# main.net
KiCad netlist of a schematic drawn in Altium Designer
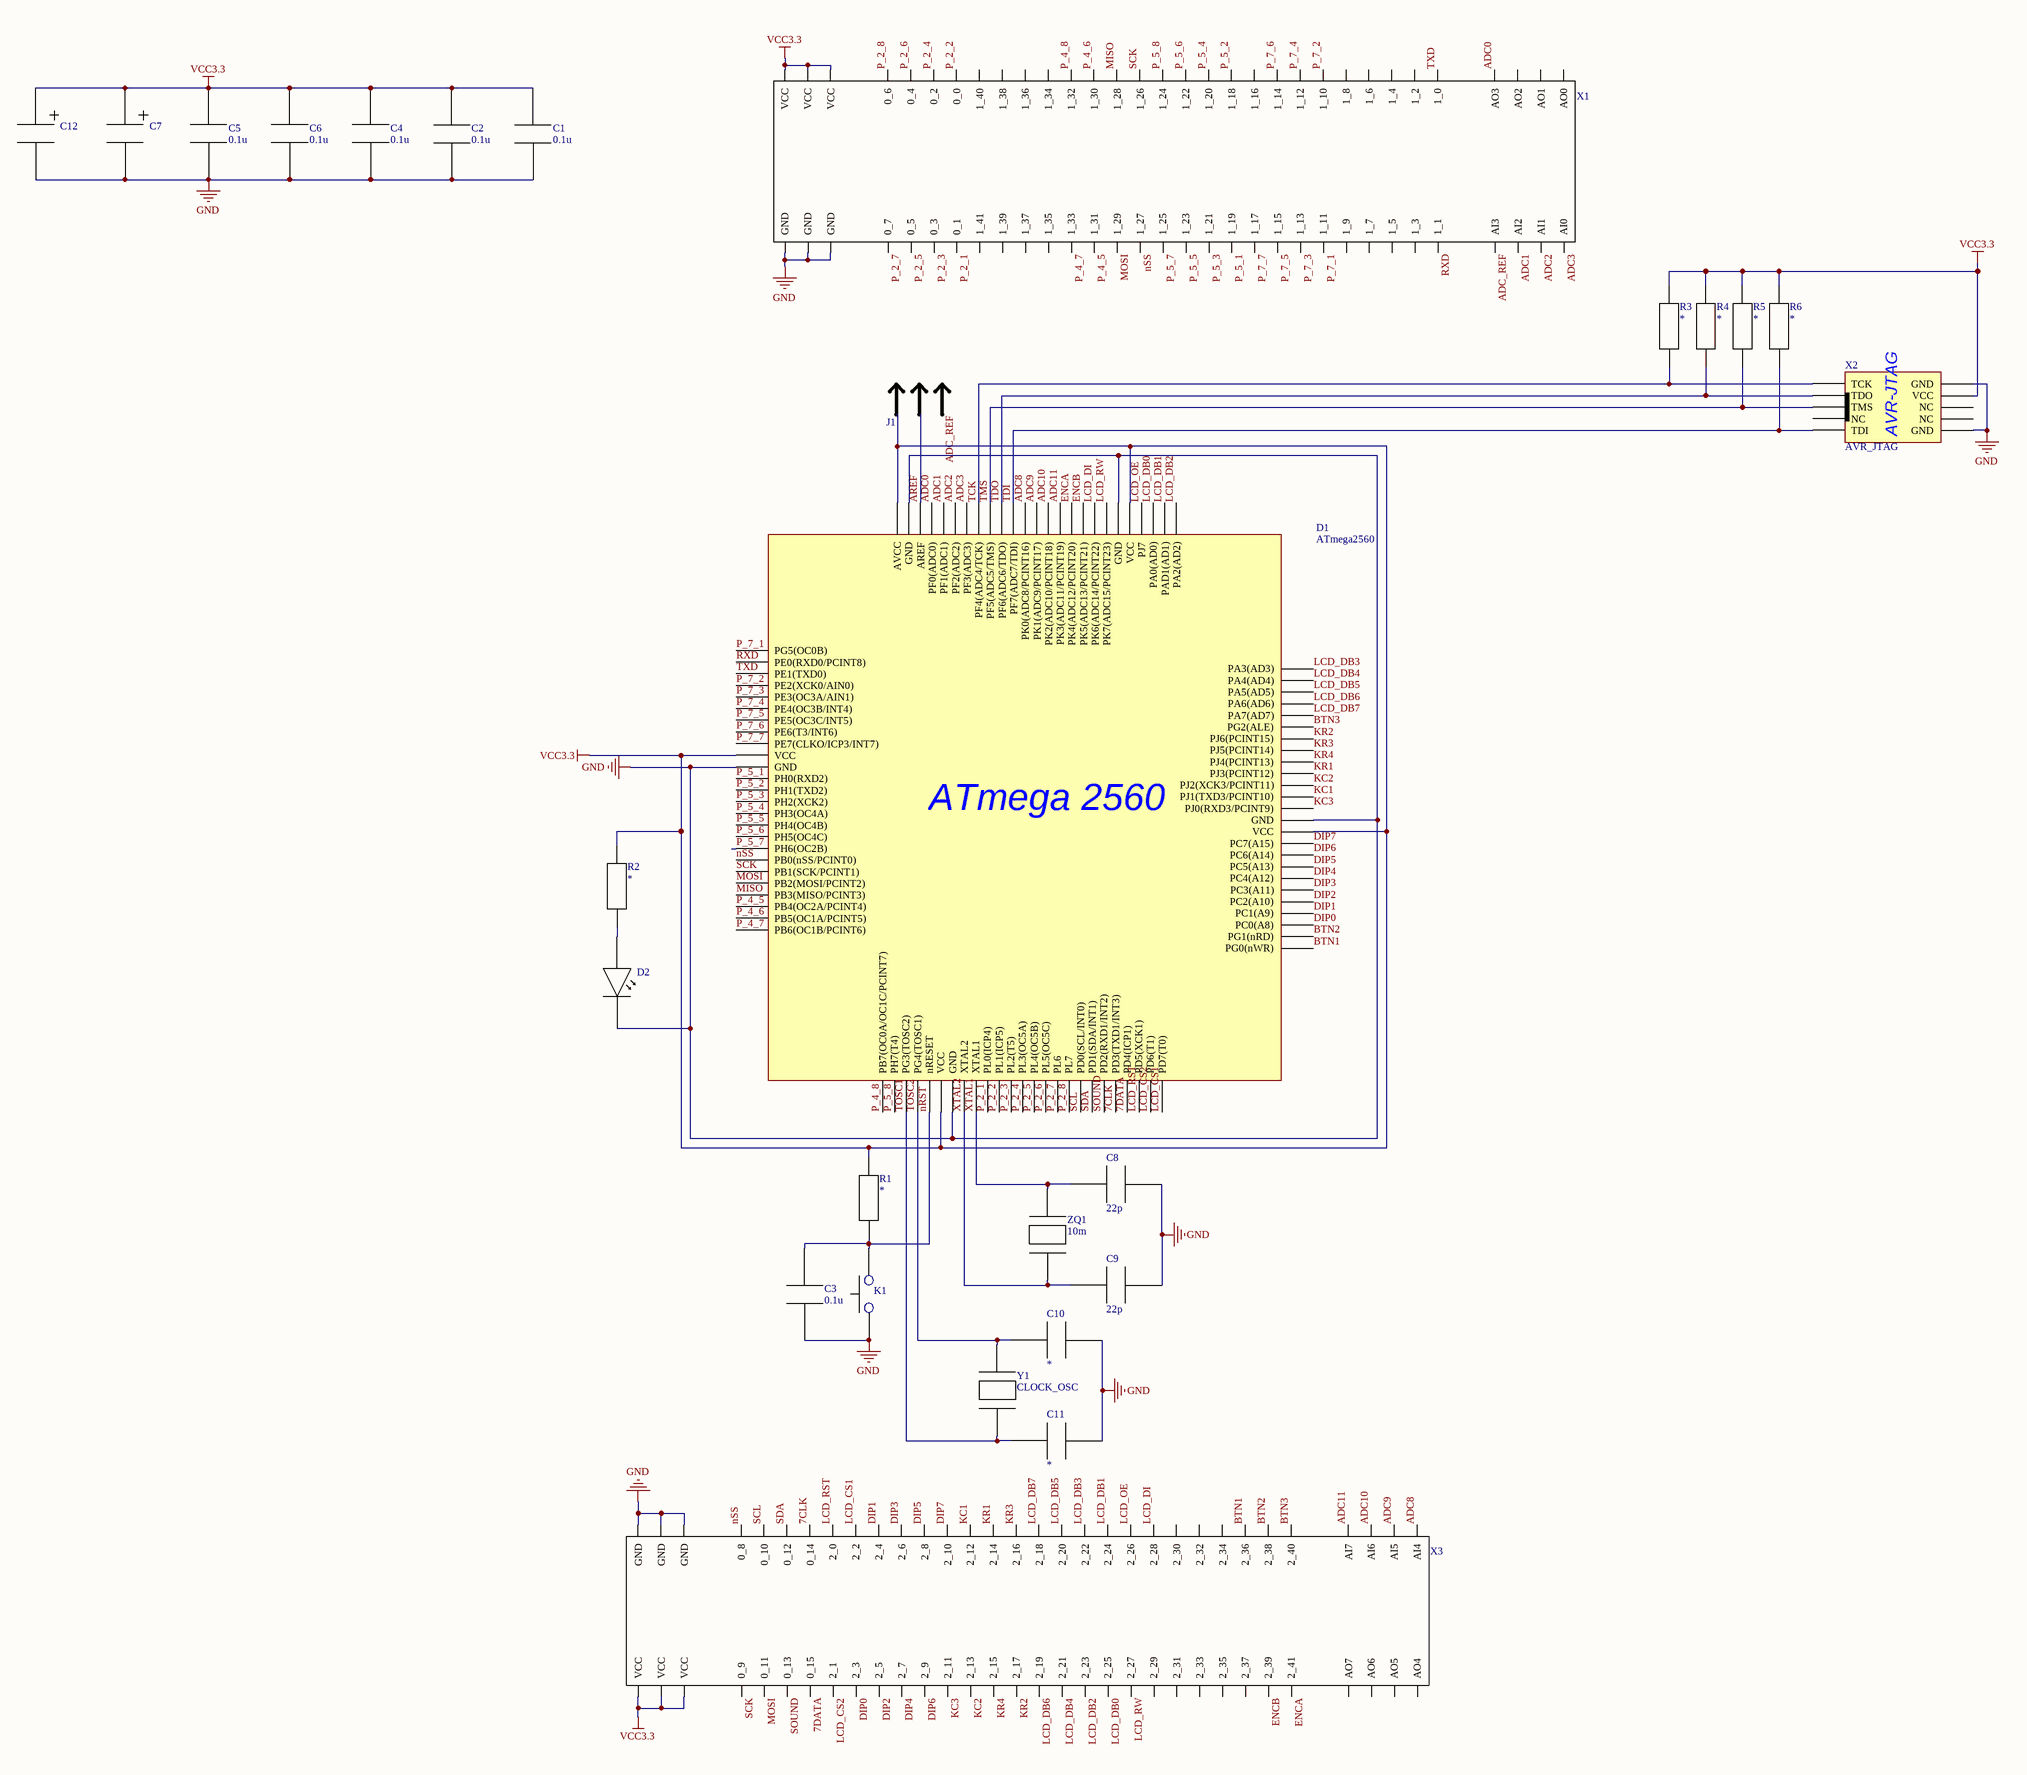
[diagram p0: main.SchDoc]

(export (version "E")
  (design (tool "Eeschema 10.0.6"))
  (components
    (comp (ref "C1")
      (value "0.1u")
      (footprint "0805")
      (description "0805 ceramic capacitor")
      (libsource (lib "ELVmega") (part "C0805"))
    )
    (comp (ref "C2")
      (value "0.1u")
      (footprint "0805")
      (description "0805 ceramic capacitor")
      (libsource (lib "ELVmega") (part "C0805"))
    )
    (comp (ref "C3")
      (value "0.1u")
      (footprint "0805")
      (description "0805 ceramic capacitor")
      (libsource (lib "ELVmega") (part "C0805"))
    )
    (comp (ref "C4")
      (value "0.1u")
      (footprint "0805")
      (description "0805 ceramic capacitor")
      (libsource (lib "ELVmega") (part "C0805"))
    )
    (comp (ref "C5")
      (value "0.1u")
      (footprint "0805")
      (description "0805 ceramic capacitor")
      (libsource (lib "ELVmega") (part "C0805"))
    )
    (comp (ref "C6")
      (value "0.1u")
      (footprint "0805")
      (description "0805 ceramic capacitor")
      (libsource (lib "ELVmega") (part "C0805"))
    )
    (comp (ref "C7")
      (value "C_Ta")
      (footprint "C_Ta")
      (description "tantalum capacitor")
      (libsource (lib "ELVmega") (part "C_Ta"))
    )
    (comp (ref "C8")
      (value "22p")
      (footprint "0805")
      (description "0805 ceramic capacitor")
      (libsource (lib "ELVmega") (part "C0805"))
    )
    (comp (ref "C9")
      (value "22p")
      (footprint "0805")
      (description "0805 ceramic capacitor")
      (libsource (lib "ELVmega") (part "C0805"))
    )
    (comp (ref "C10")
      (value "*")
      (footprint "0805")
      (description "0805 ceramic capacitor")
      (libsource (lib "ELVmega") (part "C0805"))
    )
    (comp (ref "C11")
      (value "*")
      (footprint "0805")
      (description "0805 ceramic capacitor")
      (libsource (lib "ELVmega") (part "C0805"))
    )
    (comp (ref "C12")
      (value "C_Ta")
      (footprint "C_Ta")
      (description "tantalum capacitor")
      (libsource (lib "spels_lib") (part "C_Ta"))
    )
    (comp (ref "D1")
      (value "ATmega2560")
      (footprint "ATmega2560-16AU")
      (libsource (lib "ELVmega") (part "ATmega2560"))
    )
    (comp (ref "D2") (value "LED0805") (footprint "0805") (libsource (lib "ELVmega") (part "LED0805")))
    (comp (ref "J1")
      (value "JUMPER_SWITCH_2S")
      (footprint "JUMPER_SWITCH_2S")
      (description "2 state jumper switch")
      (libsource (lib "ELVmega") (part "JUMPER_SWITCH_2S"))
    )
    (comp (ref "K1")
      (value "SMD_BUTTON")
      (footprint "SMD_BUTTON")
      (description "smd micro button")
      (libsource (lib "ELVmega") (part "SMD_BUTTON"))
    )
    (comp (ref "R1")
      (value "*")
      (footprint "0805")
      (description "0805 resistor")
      (libsource (lib "") (part "R0805_1"))
    )
    (comp (ref "R2")
      (value "*")
      (footprint "0805")
      (description "0805 resistor")
      (libsource (lib "ELVmega") (part "R0805"))
    )
    (comp (ref "R3")
      (value "*")
      (footprint "0805")
      (description "0805 resistor")
      (libsource (lib "") (part "R0805_1"))
    )
    (comp (ref "R4")
      (value "*")
      (footprint "0805")
      (description "0805 resistor")
      (libsource (lib "") (part "R0805_1"))
    )
    (comp (ref "R5")
      (value "*")
      (footprint "0805")
      (description "0805 resistor")
      (libsource (lib "") (part "R0805_1"))
    )
    (comp (ref "R6")
      (value "*")
      (footprint "0805")
      (description "0805 resistor")
      (libsource (lib "") (part "R0805_1"))
    )
    (comp (ref "X1")
      (value "CONNECTOR_TOP")
      (footprint "Connector")
      (description "control board connector")
      (libsource (lib "elvis_lib") (part "CONNECTOR_TOP"))
    )
    (comp (ref "X2") (value "AVR_JTAG") (footprint "JTAG_PLD") (libsource (lib "ELVmega") (part "AVR_JTAG")))
    (comp (ref "X3")
      (value "CONNECTOR_BOTTOM")
      (footprint "Connector")
      (description "control board connector")
      (libsource (lib "elvis_lib") (part "CONNECTOR_BOTTOM"))
    )
    (comp (ref "Y1")
      (value "CLOCK_OSC")
      (footprint "CLOCK_OSC")
      (description "low speed external clock")
      (libsource (lib "ELVmega") (part "CLOCK_OSC"))
    )
    (comp (ref "ZQ1") (value "10m") (footprint "XTAL") (libsource (lib "ELVmega") (part "XTAL")))
  )
  (nets
    (net (code "1") (name "/7CLK") (class "Default")
      (node (ref "D1") (pin "46") (pinfunction "PD3(TXD1/INT3)_46") (pintype "passive"))
      (node (ref "X3") (pin "6") (pinfunction "0_14_6") (pintype "passive"))
    )
    (net (code "2") (name "/7DATA") (class "Default")
      (node (ref "D1") (pin "47") (pinfunction "PD4(ICP1)_47") (pintype "passive"))
      (node (ref "X3") (pin "57") (pinfunction "0_15_57") (pintype "passive"))
    )
    (net (code "3") (name "/ADC0") (class "Default")
      (node (ref "D1") (pin "97") (pinfunction "PF0(ADC0)_97") (pintype "passive"))
      (node (ref "X1") (pin "28") (pinfunction "AO3_28") (pintype "passive"))
    )
    (net (code "4") (name "/ADC1") (class "Default")
      (node (ref "D1") (pin "96") (pinfunction "PF1(ADC1)_96") (pintype "passive"))
      (node (ref "X1") (pin "34") (pinfunction "AI2_34") (pintype "passive"))
    )
    (net (code "5") (name "/ADC2") (class "Default")
      (node (ref "D1") (pin "95") (pinfunction "PF2(ADC2)_95") (pintype "passive"))
      (node (ref "X1") (pin "33") (pinfunction "AI1_33") (pintype "passive"))
    )
    (net (code "6") (name "/ADC3") (class "Default")
      (node (ref "D1") (pin "94") (pinfunction "PF3(ADC3)_94") (pintype "passive"))
      (node (ref "X1") (pin "32") (pinfunction "AI0_32") (pintype "passive"))
    )
    (net (code "7") (name "/ADC8") (class "Default")
      (node (ref "D1") (pin "89") (pinfunction "PK0(ADC8/PCINT16)_89") (pintype "passive"))
      (node (ref "X3") (pin "31") (pinfunction "AI4_31") (pintype "passive"))
    )
    (net (code "8") (name "/ADC9") (class "Default")
      (node (ref "D1") (pin "88") (pinfunction "PK1(ADC9/PCINT17)_88") (pintype "passive"))
      (node (ref "X3") (pin "30") (pinfunction "AI5_30") (pintype "passive"))
    )
    (net (code "9") (name "/ADC10") (class "Default")
      (node (ref "D1") (pin "87") (pinfunction "PK2(ADC10/PCINT18)_87") (pintype "passive"))
      (node (ref "X3") (pin "29") (pinfunction "AI6_29") (pintype "passive"))
    )
    (net (code "10") (name "/ADC11") (class "Default")
      (node (ref "D1") (pin "86") (pinfunction "PK3(ADC11/PCINT19)_86") (pintype "passive"))
      (node (ref "X3") (pin "28") (pinfunction "AI7_28") (pintype "passive"))
    )
    (net (code "11") (name "/ADC_REF") (class "Default")
      (node (ref "J1") (pin "2") (pinfunction "2_2") (pintype "passive"))
      (node (ref "X1") (pin "35") (pinfunction "AI3_35") (pintype "passive"))
    )
    (net (code "12") (name "/AREF") (class "Default")
      (node (ref "D1") (pin "98") (pinfunction "AREF_98") (pintype "passive"))
      (node (ref "J1") (pin "0") (pinfunction "0_0") (pintype "passive"))
    )
    (net (code "13") (name "/BTN1") (class "Default")
      (node (ref "D1") (pin "51") (pinfunction "PG0(nWR)_51") (pintype "passive"))
      (node (ref "X3") (pin "25") (pinfunction "2_36_25") (pintype "passive"))
    )
    (net (code "14") (name "/BTN2") (class "Default")
      (node (ref "D1") (pin "52") (pinfunction "PG1(nRD)_52") (pintype "passive"))
      (node (ref "X3") (pin "26") (pinfunction "2_38_26") (pintype "passive"))
    )
    (net (code "15") (name "/BTN3") (class "Default")
      (node (ref "D1") (pin "70") (pinfunction "PG2(ALE)_70") (pintype "passive"))
      (node (ref "X3") (pin "27") (pinfunction "2_40_27") (pintype "passive"))
    )
    (net (code "16") (name "/DIP0") (class "Default")
      (node (ref "D1") (pin "53") (pinfunction "PC0(A8)_53") (pintype "passive"))
      (node (ref "X3") (pin "55") (pinfunction "2_3_55") (pintype "passive"))
    )
    (net (code "17") (name "/DIP1") (class "Default")
      (node (ref "D1") (pin "54") (pinfunction "PC1(A9)_54") (pintype "passive"))
      (node (ref "X3") (pin "9") (pinfunction "2_4_9") (pintype "passive"))
    )
    (net (code "18") (name "/DIP2") (class "Default")
      (node (ref "D1") (pin "55") (pinfunction "PC2(A10)_55") (pintype "passive"))
      (node (ref "X3") (pin "54") (pinfunction "2_5_54") (pintype "passive"))
    )
    (net (code "19") (name "/DIP3") (class "Default")
      (node (ref "D1") (pin "56") (pinfunction "PC3(A11)_56") (pintype "passive"))
      (node (ref "X3") (pin "10") (pinfunction "2_6_10") (pintype "passive"))
    )
    (net (code "20") (name "/DIP4") (class "Default")
      (node (ref "D1") (pin "57") (pinfunction "PC4(A12)_57") (pintype "passive"))
      (node (ref "X3") (pin "53") (pinfunction "2_7_53") (pintype "passive"))
    )
    (net (code "21") (name "/DIP5") (class "Default")
      (node (ref "D1") (pin "58") (pinfunction "PC5(A13)_58") (pintype "passive"))
      (node (ref "X3") (pin "11") (pinfunction "2_8_11") (pintype "passive"))
    )
    (net (code "22") (name "/DIP6") (class "Default")
      (node (ref "D1") (pin "59") (pinfunction "PC6(A14)_59") (pintype "passive"))
      (node (ref "X3") (pin "52") (pinfunction "2_9_52") (pintype "passive"))
    )
    (net (code "23") (name "/DIP7") (class "Default")
      (node (ref "D1") (pin "60") (pinfunction "PC7(A15)_60") (pintype "passive"))
      (node (ref "X3") (pin "12") (pinfunction "2_10_12") (pintype "passive"))
    )
    (net (code "24") (name "/ENCA") (class "Default")
      (node (ref "D1") (pin "85") (pinfunction "PK4(ADC12/PCINT20)_85") (pintype "passive"))
      (node (ref "X3") (pin "36") (pinfunction "2_41_36") (pintype "passive"))
    )
    (net (code "25") (name "/ENCB") (class "Default")
      (node (ref "D1") (pin "84") (pinfunction "PK5(ADC13/PCINT21)_84") (pintype "passive"))
      (node (ref "X3") (pin "37") (pinfunction "2_39_37") (pintype "passive"))
    )
    (net (code "26") (name "/KC1") (class "Default")
      (node (ref "D1") (pin "64") (pinfunction "PJ1(TXD3/PCINT10)_64") (pintype "passive"))
      (node (ref "X3") (pin "13") (pinfunction "2_12_13") (pintype "passive"))
    )
    (net (code "27") (name "/KC2") (class "Default")
      (node (ref "D1") (pin "65") (pinfunction "PJ2(XCK3/PCINT11)_65") (pintype "passive"))
      (node (ref "X3") (pin "50") (pinfunction "2_13_50") (pintype "passive"))
    )
    (net (code "28") (name "/KC3") (class "Default")
      (node (ref "D1") (pin "63") (pinfunction "PJ0(RXD3/PCINT9)_63") (pintype "passive"))
      (node (ref "X3") (pin "51") (pinfunction "2_11_51") (pintype "passive"))
    )
    (net (code "29") (name "/KR1") (class "Default")
      (node (ref "D1") (pin "66") (pinfunction "PJ3(PCINT12)_66") (pintype "passive"))
      (node (ref "X3") (pin "14") (pinfunction "2_14_14") (pintype "passive"))
    )
    (net (code "30") (name "/KR2") (class "Default")
      (node (ref "D1") (pin "69") (pinfunction "PJ6(PCINT15)_69") (pintype "passive"))
      (node (ref "X3") (pin "48") (pinfunction "2_17_48") (pintype "passive"))
    )
    (net (code "31") (name "/KR3") (class "Default")
      (node (ref "D1") (pin "68") (pinfunction "PJ5(PCINT14)_68") (pintype "passive"))
      (node (ref "X3") (pin "15") (pinfunction "2_16_15") (pintype "passive"))
    )
    (net (code "32") (name "/KR4") (class "Default")
      (node (ref "D1") (pin "67") (pinfunction "PJ4(PCINT13)_67") (pintype "passive"))
      (node (ref "X3") (pin "49") (pinfunction "2_15_49") (pintype "passive"))
    )
    (net (code "33") (name "/LCD_CS1") (class "Default")
      (node (ref "D1") (pin "50") (pinfunction "PD7(T0)_50") (pintype "passive"))
      (node (ref "X3") (pin "8") (pinfunction "2_2_8") (pintype "passive"))
    )
    (net (code "34") (name "/LCD_CS2") (class "Default")
      (node (ref "D1") (pin "49") (pinfunction "PD6(T1)_49") (pintype "passive"))
      (node (ref "X3") (pin "56") (pinfunction "2_1_56") (pintype "passive"))
    )
    (net (code "35") (name "/LCD_DB0") (class "Default")
      (node (ref "D1") (pin "78") (pinfunction "PA0(AD0)_78") (pintype "passive"))
      (node (ref "X3") (pin "44") (pinfunction "2_25_44") (pintype "passive"))
    )
    (net (code "36") (name "/LCD_DB1") (class "Default")
      (node (ref "D1") (pin "77") (pinfunction "PAD1(AD1)_77") (pintype "passive"))
      (node (ref "X3") (pin "19") (pinfunction "2_24_19") (pintype "passive"))
    )
    (net (code "37") (name "/LCD_DB2") (class "Default")
      (node (ref "D1") (pin "76") (pinfunction "PA2(AD2)_76") (pintype "passive"))
      (node (ref "X3") (pin "45") (pinfunction "2_23_45") (pintype "passive"))
    )
    (net (code "38") (name "/LCD_DB3") (class "Default")
      (node (ref "D1") (pin "75") (pinfunction "PA3(AD3)_75") (pintype "passive"))
      (node (ref "X3") (pin "18") (pinfunction "2_22_18") (pintype "passive"))
    )
    (net (code "39") (name "/LCD_DB4") (class "Default")
      (node (ref "D1") (pin "74") (pinfunction "PA4(AD4)_74") (pintype "passive"))
      (node (ref "X3") (pin "46") (pinfunction "2_21_46") (pintype "passive"))
    )
    (net (code "40") (name "/LCD_DB5") (class "Default")
      (node (ref "D1") (pin "73") (pinfunction "PA5(AD5)_73") (pintype "passive"))
      (node (ref "X3") (pin "17") (pinfunction "2_20_17") (pintype "passive"))
    )
    (net (code "41") (name "/LCD_DB6") (class "Default")
      (node (ref "D1") (pin "72") (pinfunction "PA6(AD6)_72") (pintype "passive"))
      (node (ref "X3") (pin "47") (pinfunction "2_19_47") (pintype "passive"))
    )
    (net (code "42") (name "/LCD_DB7") (class "Default")
      (node (ref "D1") (pin "71") (pinfunction "PA7(AD7)_71") (pintype "passive"))
      (node (ref "X3") (pin "16") (pinfunction "2_18_16") (pintype "passive"))
    )
    (net (code "43") (name "/LCD_DI") (class "Default")
      (node (ref "D1") (pin "83") (pinfunction "PK6(ADC14/PCINT22)_83") (pintype "passive"))
      (node (ref "X3") (pin "21") (pinfunction "2_28_21") (pintype "passive"))
    )
    (net (code "44") (name "/LCD_OE") (class "Default")
      (node (ref "D1") (pin "79") (pinfunction "PJ7_79") (pintype "passive"))
      (node (ref "X3") (pin "20") (pinfunction "2_26_20") (pintype "passive"))
    )
    (net (code "45") (name "/LCD_RST") (class "Default")
      (node (ref "D1") (pin "48") (pinfunction "PD5(XCK1)_48") (pintype "passive"))
      (node (ref "X3") (pin "7") (pinfunction "2_0_7") (pintype "passive"))
    )
    (net (code "46") (name "/LCD_RW") (class "Default")
      (node (ref "D1") (pin "82") (pinfunction "PK7(ADC15/PCINT23)_82") (pintype "passive"))
      (node (ref "X3") (pin "43") (pinfunction "2_27_43") (pintype "passive"))
    )
    (net (code "47") (name "/MISO") (class "Default")
      (node (ref "D1") (pin "22") (pinfunction "PB3(MISO/PCINT3)_22") (pintype "passive"))
      (node (ref "X1") (pin "13") (pinfunction "1_28_13") (pintype "passive"))
    )
    (net (code "48") (name "/MOSI") (class "Default")
      (node (ref "D1") (pin "21") (pinfunction "PB2(MOSI/PCINT2)_21") (pintype "passive"))
      (node (ref "X1") (pin "50") (pinfunction "1_29_50") (pintype "passive"))
      (node (ref "X3") (pin "59") (pinfunction "0_11_59") (pintype "passive"))
    )
    (net (code "49") (name "/P_2_1") (class "Default")
      (node (ref "D1") (pin "35") (pinfunction "PL0(ICP4)_35") (pintype "passive"))
      (node (ref "X1") (pin "57") (pinfunction "0_1_57") (pintype "passive"))
    )
    (net (code "50") (name "/P_2_2") (class "Default")
      (node (ref "D1") (pin "36") (pinfunction "PL1(ICP5)_36") (pintype "passive"))
      (node (ref "X1") (pin "6") (pinfunction "0_0_6") (pintype "passive"))
    )
    (net (code "51") (name "/P_2_3") (class "Default")
      (node (ref "D1") (pin "37") (pinfunction "PL2(T5)_37") (pintype "passive"))
      (node (ref "X1") (pin "58") (pinfunction "0_3_58") (pintype "passive"))
    )
    (net (code "52") (name "/P_2_4") (class "Default")
      (node (ref "D1") (pin "38") (pinfunction "PL3(OC5A)_38") (pintype "passive"))
      (node (ref "X1") (pin "5") (pinfunction "0_2_5") (pintype "passive"))
    )
    (net (code "53") (name "/P_2_5") (class "Default")
      (node (ref "D1") (pin "39") (pinfunction "PL4(OC5B)_39") (pintype "passive"))
      (node (ref "X1") (pin "59") (pinfunction "0_5_59") (pintype "passive"))
    )
    (net (code "54") (name "/P_2_6") (class "Default")
      (node (ref "D1") (pin "40") (pinfunction "PL5(OC5C)_40") (pintype "passive"))
      (node (ref "X1") (pin "4") (pinfunction "0_4_4") (pintype "passive"))
    )
    (net (code "55") (name "/P_2_7") (class "Default")
      (node (ref "D1") (pin "41") (pinfunction "PL6_41") (pintype "passive"))
      (node (ref "X1") (pin "60") (pinfunction "0_7_60") (pintype "passive"))
    )
    (net (code "56") (name "/P_2_8") (class "Default")
      (node (ref "D1") (pin "42") (pinfunction "PL7_42") (pintype "passive"))
      (node (ref "X1") (pin "3") (pinfunction "0_6_3") (pintype "passive"))
    )
    (net (code "57") (name "/P_4_5") (class "Default")
      (node (ref "D1") (pin "23") (pinfunction "PB4(OC2A/PCINT4)_23") (pintype "passive"))
      (node (ref "X1") (pin "51") (pinfunction "1_31_51") (pintype "passive"))
    )
    (net (code "58") (name "/P_4_6") (class "Default")
      (node (ref "D1") (pin "24") (pinfunction "PB5(OC1A/PCINT5)_24") (pintype "passive"))
      (node (ref "X1") (pin "12") (pinfunction "1_30_12") (pintype "passive"))
    )
    (net (code "59") (name "/P_4_7") (class "Default")
      (node (ref "D1") (pin "25") (pinfunction "PB6(OC1B/PCINT6)_25") (pintype "passive"))
      (node (ref "X1") (pin "52") (pinfunction "1_33_52") (pintype "passive"))
    )
    (net (code "60") (name "/P_4_8") (class "Default")
      (node (ref "D1") (pin "26") (pinfunction "PB7(OC0A/OC1C/PCINT7)_26") (pintype "passive"))
      (node (ref "X1") (pin "11") (pinfunction "1_32_11") (pintype "passive"))
    )
    (net (code "61") (name "/P_5_1") (class "Default")
      (node (ref "D1") (pin "12") (pinfunction "PH0(RXD2)_12") (pintype "passive"))
      (node (ref "X1") (pin "45") (pinfunction "1_19_45") (pintype "passive"))
    )
    (net (code "62") (name "/P_5_2") (class "Default")
      (node (ref "D1") (pin "13") (pinfunction "PH1(TXD2)_13") (pintype "passive"))
      (node (ref "X1") (pin "18") (pinfunction "1_18_18") (pintype "passive"))
    )
    (net (code "63") (name "/P_5_3") (class "Default")
      (node (ref "D1") (pin "14") (pinfunction "PH2(XCK2)_14") (pintype "passive"))
      (node (ref "X1") (pin "46") (pinfunction "1_21_46") (pintype "passive"))
    )
    (net (code "64") (name "/P_5_4") (class "Default")
      (node (ref "D1") (pin "15") (pinfunction "PH3(OC4A)_15") (pintype "passive"))
      (node (ref "X1") (pin "17") (pinfunction "1_20_17") (pintype "passive"))
    )
    (net (code "65") (name "/P_5_5") (class "Default")
      (node (ref "D1") (pin "16") (pinfunction "PH4(OC4B)_16") (pintype "passive"))
      (node (ref "X1") (pin "47") (pinfunction "1_23_47") (pintype "passive"))
    )
    (net (code "66") (name "/P_5_6") (class "Default")
      (node (ref "D1") (pin "17") (pinfunction "PH5(OC4C)_17") (pintype "passive"))
      (node (ref "X1") (pin "16") (pinfunction "1_22_16") (pintype "passive"))
    )
    (net (code "67") (name "/P_5_7") (class "Default")
      (node (ref "D1") (pin "18") (pinfunction "PH6(OC2B)_18") (pintype "passive"))
      (node (ref "X1") (pin "48") (pinfunction "1_25_48") (pintype "passive"))
    )
    (net (code "68") (name "/P_5_8") (class "Default")
      (node (ref "D1") (pin "27") (pinfunction "PH7(T4)_27") (pintype "passive"))
      (node (ref "X1") (pin "15") (pinfunction "1_24_15") (pintype "passive"))
    )
    (net (code "69") (name "/P_7_1") (class "Default")
      (node (ref "D1") (pin "1") (pinfunction "PG5(OC0B)_1") (pintype "passive"))
      (node (ref "X1") (pin "41") (pinfunction "1_11_41") (pintype "passive"))
    )
    (net (code "70") (name "/P_7_2") (class "Default")
      (node (ref "D1") (pin "4") (pinfunction "PE2(XCK0/AIN0)_4") (pintype "passive"))
      (node (ref "X1") (pin "22") (pinfunction "1_10_22") (pintype "passive"))
    )
    (net (code "71") (name "/P_7_3") (class "Default")
      (node (ref "D1") (pin "5") (pinfunction "PE3(OC3A/AIN1)_5") (pintype "passive"))
      (node (ref "X1") (pin "42") (pinfunction "1_13_42") (pintype "passive"))
    )
    (net (code "72") (name "/P_7_4") (class "Default")
      (node (ref "D1") (pin "6") (pinfunction "PE4(OC3B/INT4)_6") (pintype "passive"))
      (node (ref "X1") (pin "21") (pinfunction "1_12_21") (pintype "passive"))
    )
    (net (code "73") (name "/P_7_5") (class "Default")
      (node (ref "D1") (pin "7") (pinfunction "PE5(OC3C/INT5)_7") (pintype "passive"))
      (node (ref "X1") (pin "43") (pinfunction "1_15_43") (pintype "passive"))
    )
    (net (code "74") (name "/P_7_6") (class "Default")
      (node (ref "D1") (pin "8") (pinfunction "PE6(T3/INT6)_8") (pintype "passive"))
      (node (ref "X1") (pin "20") (pinfunction "1_14_20") (pintype "passive"))
    )
    (net (code "75") (name "/P_7_7") (class "Default")
      (node (ref "D1") (pin "9") (pinfunction "PE7(CLKO/ICP3/INT7)_9") (pintype "passive"))
      (node (ref "X1") (pin "44") (pinfunction "1_17_44") (pintype "passive"))
    )
    (net (code "76") (name "/RXD") (class "Default")
      (node (ref "D1") (pin "2") (pinfunction "PE0(RXD0/PCINT8)_2") (pintype "passive"))
      (node (ref "X1") (pin "36") (pinfunction "1_1_36") (pintype "passive"))
    )
    (net (code "77") (name "/SCK") (class "Default")
      (node (ref "D1") (pin "20") (pinfunction "PB1(SCK/PCINT1)_20") (pintype "passive"))
      (node (ref "X1") (pin "14") (pinfunction "1_26_14") (pintype "passive"))
      (node (ref "X3") (pin "60") (pinfunction "0_9_60") (pintype "passive"))
    )
    (net (code "78") (name "/SCL") (class "Default")
      (node (ref "D1") (pin "43") (pinfunction "PD0(SCL/INT0)_43") (pintype "passive"))
      (node (ref "X3") (pin "4") (pinfunction "0_10_4") (pintype "passive"))
    )
    (net (code "79") (name "/SDA") (class "Default")
      (node (ref "D1") (pin "44") (pinfunction "PD1(SDA/INT1)_44") (pintype "passive"))
      (node (ref "X3") (pin "5") (pinfunction "0_12_5") (pintype "passive"))
    )
    (net (code "80") (name "/SOUND") (class "Default")
      (node (ref "D1") (pin "45") (pinfunction "PD2(RXD1/INT2)_45") (pintype "passive"))
      (node (ref "X3") (pin "58") (pinfunction "0_13_58") (pintype "passive"))
    )
    (net (code "81") (name "/TCK") (class "Default")
      (node (ref "D1") (pin "93") (pinfunction "PF4(ADC4/TCK)_93") (pintype "passive"))
      (node (ref "R3") (pin "1") (pinfunction "1_1") (pintype "passive"))
      (node (ref "X2") (pin "1") (pinfunction "TCK_1") (pintype "passive"))
    )
    (net (code "82") (name "/TDI") (class "Default")
      (node (ref "D1") (pin "90") (pinfunction "PF7(ADC7/TDI)_90") (pintype "passive"))
      (node (ref "R6") (pin "1") (pinfunction "1_1") (pintype "passive"))
      (node (ref "X2") (pin "9") (pinfunction "TDI_9") (pintype "passive"))
    )
    (net (code "83") (name "/TDO") (class "Default")
      (node (ref "D1") (pin "91") (pinfunction "PF6(ADC6/TDO)_91") (pintype "passive"))
      (node (ref "R4") (pin "1") (pinfunction "1_1") (pintype "passive"))
      (node (ref "X2") (pin "3") (pinfunction "TDO_3") (pintype "passive"))
    )
    (net (code "84") (name "/TMS") (class "Default")
      (node (ref "D1") (pin "92") (pinfunction "PF5(ADC5/TMS)_92") (pintype "passive"))
      (node (ref "R5") (pin "1") (pinfunction "1_1") (pintype "passive"))
      (node (ref "X2") (pin "5") (pinfunction "TMS_5") (pintype "passive"))
    )
    (net (code "85") (name "/TOSC1") (class "Default")
      (node (ref "C11") (pin "2") (pinfunction "2_2") (pintype "passive"))
      (node (ref "D1") (pin "28") (pinfunction "PG3(TOSC2)_28") (pintype "passive"))
      (node (ref "Y1") (pin "2") (pinfunction "2_2") (pintype "passive"))
    )
    (net (code "86") (name "/TOSC2") (class "Default")
      (node (ref "C10") (pin "2") (pinfunction "2_2") (pintype "passive"))
      (node (ref "D1") (pin "29") (pinfunction "PG4(TOSC1)_29") (pintype "passive"))
      (node (ref "Y1") (pin "1") (pinfunction "1_1") (pintype "passive"))
    )
    (net (code "87") (name "/TXD") (class "Default")
      (node (ref "D1") (pin "3") (pinfunction "PE1(TXD0)_3") (pintype "passive"))
      (node (ref "X1") (pin "27") (pinfunction "1_0_27") (pintype "passive"))
    )
    (net (code "88") (name "/XTAL1") (class "Default")
      (node (ref "C8") (pin "2") (pinfunction "2_2") (pintype "passive"))
      (node (ref "D1") (pin "34") (pinfunction "XTAL1_34") (pintype "passive"))
      (node (ref "ZQ1") (pin "2") (pinfunction "2_2") (pintype "passive"))
    )
    (net (code "89") (name "/XTAL2") (class "Default")
      (node (ref "C9") (pin "2") (pinfunction "2_2") (pintype "passive"))
      (node (ref "D1") (pin "33") (pinfunction "XTAL2_33") (pintype "passive"))
      (node (ref "ZQ1") (pin "1") (pinfunction "1_1") (pintype "passive"))
    )
    (net (code "90") (name "/nRST") (class "Default")
      (node (ref "C3") (pin "2") (pinfunction "2_2") (pintype "passive"))
      (node (ref "D1") (pin "30") (pinfunction "nRESET_30") (pintype "passive"))
      (node (ref "K1") (pin "2") (pinfunction "2_2") (pintype "passive"))
      (node (ref "R1") (pin "2") (pinfunction "2_2") (pintype "passive"))
    )
    (net (code "91") (name "/nSS") (class "Default")
      (node (ref "D1") (pin "19") (pinfunction "PB0(nSS/PCINT0)_19") (pintype "passive"))
      (node (ref "X1") (pin "49") (pinfunction "1_27_49") (pintype "passive"))
      (node (ref "X3") (pin "3") (pinfunction "0_8_3") (pintype "passive"))
    )
    (net (code "92") (name "GND") (class "Default")
      (node (ref "C1") (pin "1") (pinfunction "1_1") (pintype "passive"))
      (node (ref "C10") (pin "1") (pinfunction "1_1") (pintype "passive"))
      (node (ref "C11") (pin "1") (pinfunction "1_1") (pintype "passive"))
      (node (ref "C12") (pin "2") (pinfunction "2_2") (pintype "passive"))
      (node (ref "C2") (pin "1") (pinfunction "1_1") (pintype "passive"))
      (node (ref "C3") (pin "1") (pinfunction "1_1") (pintype "passive"))
      (node (ref "C4") (pin "2") (pinfunction "2_2") (pintype "passive"))
      (node (ref "C5") (pin "2") (pinfunction "2_2") (pintype "passive"))
      (node (ref "C6") (pin "2") (pinfunction "2_2") (pintype "passive"))
      (node (ref "C7") (pin "2") (pinfunction "2_2") (pintype "passive"))
      (node (ref "C8") (pin "1") (pinfunction "1_1") (pintype "passive"))
      (node (ref "C9") (pin "1") (pinfunction "1_1") (pintype "passive"))
      (node (ref "D1") (pin "11") (pinfunction "GND_11") (pintype "passive"))
      (node (ref "D1") (pin "32") (pinfunction "GND_32") (pintype "passive"))
      (node (ref "D1") (pin "62") (pinfunction "GND_62") (pintype "passive"))
      (node (ref "D1") (pin "81") (pinfunction "GND_81") (pintype "passive"))
      (node (ref "D1") (pin "99") (pinfunction "GND_99") (pintype "passive"))
      (node (ref "D2") (pin "2") (pinfunction "2_2") (pintype "passive"))
      (node (ref "K1") (pin "1") (pinfunction "1_1") (pintype "passive"))
      (node (ref "X1") (pin "61") (pinfunction "GND_61") (pintype "passive"))
      (node (ref "X1") (pin "62") (pinfunction "GND_62") (pintype "passive"))
      (node (ref "X1") (pin "63") (pinfunction "GND_63") (pintype "passive"))
      (node (ref "X2") (pin "10") (pinfunction "GND_10") (pintype "passive"))
      (node (ref "X2") (pin "2") (pinfunction "GND_2") (pintype "passive"))
      (node (ref "X3") (pin "0") (pinfunction "GND_0") (pintype "passive"))
      (node (ref "X3") (pin "1") (pinfunction "GND_1") (pintype "passive"))
      (node (ref "X3") (pin "2") (pinfunction "GND_2") (pintype "passive"))
    )
    (net (code "93") (name "Net-(D2-Pad1)") (class "Default")
      (node (ref "D2") (pin "1") (pinfunction "1_1") (pintype "passive"))
      (node (ref "R2") (pin "2") (pinfunction "2_2") (pintype "passive"))
    )
    (net (code "94") (name "VCC3.3") (class "Default")
      (node (ref "C1") (pin "2") (pinfunction "2_2") (pintype "passive"))
      (node (ref "C12") (pin "1") (pinfunction "1_1") (pintype "passive"))
      (node (ref "C2") (pin "2") (pinfunction "2_2") (pintype "passive"))
      (node (ref "C4") (pin "1") (pinfunction "1_1") (pintype "passive"))
      (node (ref "C5") (pin "1") (pinfunction "1_1") (pintype "passive"))
      (node (ref "C6") (pin "1") (pinfunction "1_1") (pintype "passive"))
      (node (ref "C7") (pin "1") (pinfunction "1_1") (pintype "passive"))
      (node (ref "D1") (pin "10") (pinfunction "VCC_10") (pintype "passive"))
      (node (ref "D1") (pin "100") (pinfunction "AVCC_100") (pintype "passive"))
      (node (ref "D1") (pin "31") (pinfunction "VCC_31") (pintype "passive"))
      (node (ref "D1") (pin "61") (pinfunction "VCC_61") (pintype "passive"))
      (node (ref "D1") (pin "80") (pinfunction "VCC_80") (pintype "passive"))
      (node (ref "J1") (pin "1") (pinfunction "1_1") (pintype "passive"))
      (node (ref "R1") (pin "1") (pinfunction "1_1") (pintype "passive"))
      (node (ref "R2") (pin "1") (pinfunction "1_1") (pintype "passive"))
      (node (ref "R3") (pin "2") (pinfunction "2_2") (pintype "passive"))
      (node (ref "R4") (pin "2") (pinfunction "2_2") (pintype "passive"))
      (node (ref "R5") (pin "2") (pinfunction "2_2") (pintype "passive"))
      (node (ref "R6") (pin "2") (pinfunction "2_2") (pintype "passive"))
      (node (ref "X1") (pin "0") (pinfunction "VCC_0") (pintype "passive"))
      (node (ref "X1") (pin "1") (pinfunction "VCC_1") (pintype "passive"))
      (node (ref "X1") (pin "2") (pinfunction "VCC_2") (pintype "passive"))
      (node (ref "X2") (pin "4") (pinfunction "VCC_4") (pintype "passive"))
      (node (ref "X3") (pin "61") (pinfunction "VCC_61") (pintype "passive"))
      (node (ref "X3") (pin "62") (pinfunction "VCC_62") (pintype "passive"))
      (node (ref "X3") (pin "63") (pinfunction "VCC_63") (pintype "passive"))
    )
    (net (code "95") (name "unconnected-(X1-1_2-Pad26)") (class "Default")
      (node (ref "X1") (pin "26") (pinfunction "1_2_26") (pintype "passive"))
    )
    (net (code "96") (name "unconnected-(X1-1_3-Pad37)") (class "Default")
      (node (ref "X1") (pin "37") (pinfunction "1_3_37") (pintype "passive"))
    )
    (net (code "97") (name "unconnected-(X1-1_4-Pad25)") (class "Default")
      (node (ref "X1") (pin "25") (pinfunction "1_4_25") (pintype "passive"))
    )
    (net (code "98") (name "unconnected-(X1-1_5-Pad38)") (class "Default")
      (node (ref "X1") (pin "38") (pinfunction "1_5_38") (pintype "passive"))
    )
    (net (code "99") (name "unconnected-(X1-1_6-Pad24)") (class "Default")
      (node (ref "X1") (pin "24") (pinfunction "1_6_24") (pintype "passive"))
    )
    (net (code "100") (name "unconnected-(X1-1_7-Pad39)") (class "Default")
      (node (ref "X1") (pin "39") (pinfunction "1_7_39") (pintype "passive"))
    )
    (net (code "101") (name "unconnected-(X1-1_8-Pad23)") (class "Default")
      (node (ref "X1") (pin "23") (pinfunction "1_8_23") (pintype "passive"))
    )
    (net (code "102") (name "unconnected-(X1-1_9-Pad40)") (class "Default")
      (node (ref "X1") (pin "40") (pinfunction "1_9_40") (pintype "passive"))
    )
    (net (code "103") (name "unconnected-(X1-1_16-Pad19)") (class "Default")
      (node (ref "X1") (pin "19") (pinfunction "1_16_19") (pintype "passive"))
    )
    (net (code "104") (name "unconnected-(X1-1_34-Pad10)") (class "Default")
      (node (ref "X1") (pin "10") (pinfunction "1_34_10") (pintype "passive"))
    )
    (net (code "105") (name "unconnected-(X1-1_35-Pad53)") (class "Default")
      (node (ref "X1") (pin "53") (pinfunction "1_35_53") (pintype "passive"))
    )
    (net (code "106") (name "unconnected-(X1-1_36-Pad9)") (class "Default")
      (node (ref "X1") (pin "9") (pinfunction "1_36_9") (pintype "passive"))
    )
    (net (code "107") (name "unconnected-(X1-1_37-Pad54)") (class "Default")
      (node (ref "X1") (pin "54") (pinfunction "1_37_54") (pintype "passive"))
    )
    (net (code "108") (name "unconnected-(X1-1_38-Pad8)") (class "Default")
      (node (ref "X1") (pin "8") (pinfunction "1_38_8") (pintype "passive"))
    )
    (net (code "109") (name "unconnected-(X1-1_39-Pad55)") (class "Default")
      (node (ref "X1") (pin "55") (pinfunction "1_39_55") (pintype "passive"))
    )
    (net (code "110") (name "unconnected-(X1-1_40-Pad7)") (class "Default")
      (node (ref "X1") (pin "7") (pinfunction "1_40_7") (pintype "passive"))
    )
    (net (code "111") (name "unconnected-(X1-1_41-Pad56)") (class "Default")
      (node (ref "X1") (pin "56") (pinfunction "1_41_56") (pintype "passive"))
    )
    (net (code "112") (name "unconnected-(X1-AO0-Pad31)") (class "Default")
      (node (ref "X1") (pin "31") (pinfunction "AO0_31") (pintype "passive"))
    )
    (net (code "113") (name "unconnected-(X1-AO1-Pad30)") (class "Default")
      (node (ref "X1") (pin "30") (pinfunction "AO1_30") (pintype "passive"))
    )
    (net (code "114") (name "unconnected-(X1-AO2-Pad29)") (class "Default")
      (node (ref "X1") (pin "29") (pinfunction "AO2_29") (pintype "passive"))
    )
    (net (code "115") (name "unconnected-(X2-NC-Pad6)") (class "Default")
      (node (ref "X2") (pin "6") (pinfunction "NC_6") (pintype "passive"))
    )
    (net (code "116") (name "unconnected-(X2-NC-Pad7)") (class "Default")
      (node (ref "X2") (pin "7") (pinfunction "NC_7") (pintype "passive"))
    )
    (net (code "117") (name "unconnected-(X2-NC-Pad8)") (class "Default")
      (node (ref "X2") (pin "8") (pinfunction "NC_8") (pintype "passive"))
    )
    (net (code "118") (name "unconnected-(X3-2_29-Pad42)") (class "Default")
      (node (ref "X3") (pin "42") (pinfunction "2_29_42") (pintype "passive"))
    )
    (net (code "119") (name "unconnected-(X3-2_30-Pad22)") (class "Default")
      (node (ref "X3") (pin "22") (pinfunction "2_30_22") (pintype "passive"))
    )
    (net (code "120") (name "unconnected-(X3-2_31-Pad41)") (class "Default")
      (node (ref "X3") (pin "41") (pinfunction "2_31_41") (pintype "passive"))
    )
    (net (code "121") (name "unconnected-(X3-2_32-Pad23)") (class "Default")
      (node (ref "X3") (pin "23") (pinfunction "2_32_23") (pintype "passive"))
    )
    (net (code "122") (name "unconnected-(X3-2_33-Pad40)") (class "Default")
      (node (ref "X3") (pin "40") (pinfunction "2_33_40") (pintype "passive"))
    )
    (net (code "123") (name "unconnected-(X3-2_34-Pad24)") (class "Default")
      (node (ref "X3") (pin "24") (pinfunction "2_34_24") (pintype "passive"))
    )
    (net (code "124") (name "unconnected-(X3-2_35-Pad39)") (class "Default")
      (node (ref "X3") (pin "39") (pinfunction "2_35_39") (pintype "passive"))
    )
    (net (code "125") (name "unconnected-(X3-2_37-Pad38)") (class "Default")
      (node (ref "X3") (pin "38") (pinfunction "2_37_38") (pintype "passive"))
    )
    (net (code "126") (name "unconnected-(X3-AO4-Pad32)") (class "Default")
      (node (ref "X3") (pin "32") (pinfunction "AO4_32") (pintype "passive"))
    )
    (net (code "127") (name "unconnected-(X3-AO5-Pad33)") (class "Default")
      (node (ref "X3") (pin "33") (pinfunction "AO5_33") (pintype "passive"))
    )
    (net (code "128") (name "unconnected-(X3-AO6-Pad34)") (class "Default")
      (node (ref "X3") (pin "34") (pinfunction "AO6_34") (pintype "passive"))
    )
    (net (code "129") (name "unconnected-(X3-AO7-Pad35)") (class "Default")
      (node (ref "X3") (pin "35") (pinfunction "AO7_35") (pintype "passive"))
    )
  )
)
